# Transmitter_Bug-BC547.net
KiCad netlist of a schematic drawn in EAGLE
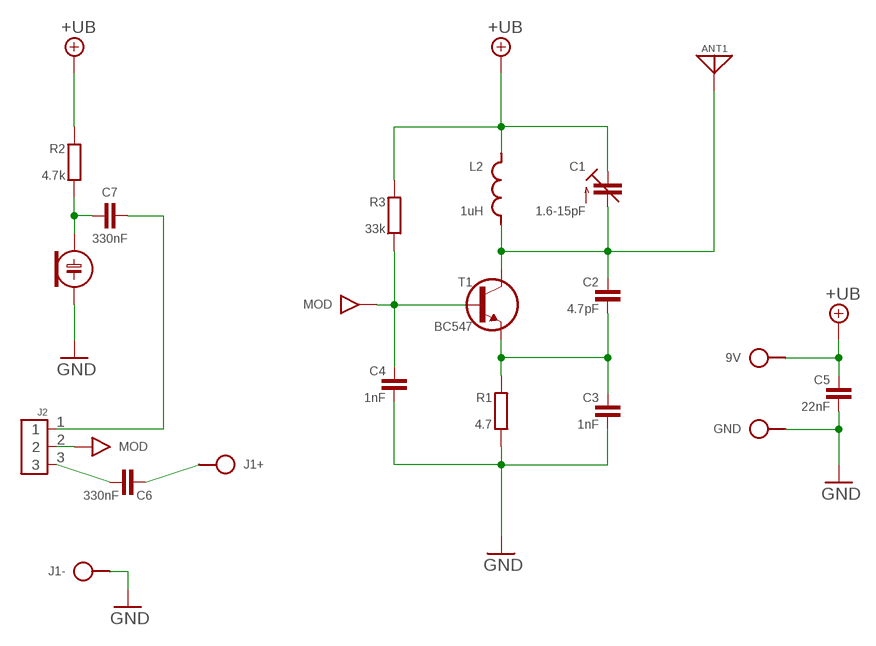
[diagram p0: schematic, sheet 1]

(export (version "E")
  (design (tool "Eeschema 10.0.6"))
  (components
    (comp (ref "9V")
      (value "SPAD")
      (footprint "eagle-import:SPAD")
      (libsource (lib "eagle-import") (part "SPAD"))
    )
    (comp (ref "ANT1")
      (value "ANT")
      (footprint "eagle-import:SPAD")
      (libsource (lib "eagle-import") (part "ANT"))
    )
    (comp (ref "C1")
      (value "1.6-15pF")
      (footprint "eagle-import:TRIM-2222-808")
      (libsource (lib "eagle-import") (part "C-TR-PH201272222-808-2PINB"))
    )
    (comp (ref "C2")
      (value "4.7pF")
      (footprint "eagle-import:C025-015X024")
      (libsource (lib "eagle-import") (part "C025-015X024"))
    )
    (comp (ref "C3")
      (value "1nF")
      (footprint "eagle-import:C025-015X024")
      (libsource (lib "eagle-import") (part "C025-015X024"))
    )
    (comp (ref "C4")
      (value "1nF")
      (footprint "eagle-import:C050-020X036_V")
      (libsource (lib "eagle-import") (part "C050-020X036/V"))
    )
    (comp (ref "C5")
      (value "22nF")
      (footprint "eagle-import:C050-020X036_V")
      (libsource (lib "eagle-import") (part "C050-020X036/V"))
    )
    (comp (ref "C6")
      (value "330nF")
      (footprint "eagle-import:C050-020X044")
      (libsource (lib "eagle-import") (part "C-H050-020X044"))
    )
    (comp (ref "C7")
      (value "330nF")
      (footprint "eagle-import:C050-020X044")
      (libsource (lib "eagle-import") (part "C050-020X044"))
    )
    (comp (ref "ECM")
      (value "ECM-4")
      (footprint "eagle-import:ECM-4")
      (libsource (lib "eagle-import") (part "ECM-4"))
    )
    (comp (ref "GND")
      (value "SPAD")
      (footprint "eagle-import:SPAD")
      (libsource (lib "eagle-import") (part "SPAD"))
    )
    (comp (ref "J1")
      (value "SPAD+--+")
      (footprint "eagle-import:SPAD-+")
      (libsource (lib "eagle-import") (part "SPAD+--+"))
    )
    (comp (ref "J2")
      (value "CONN-3P-3P")
      (footprint "eagle-import:CONN-3P")
      (libsource (lib "eagle-import") (part "CONN-3P-3P"))
    )
    (comp (ref "L2")
      (value "1uH")
      (footprint "eagle-import:L-04_7V-X")
      (libsource (lib "eagle-import") (part "L-SHORT04/7V-X"))
    )
    (comp (ref "R1")
      (value "4.7")
      (footprint "eagle-import:0204_2V")
      (libsource (lib "eagle-import") (part "R0204/2V"))
    )
    (comp (ref "R2")
      (value "4.7k")
      (footprint "eagle-import:0202_7-V")
      (libsource (lib "eagle-import") (part "R0202/7-V"))
    )
    (comp (ref "R3")
      (value "33k")
      (footprint "eagle-import:0202_7-V")
      (libsource (lib "eagle-import") (part "R0202/7-V"))
    )
    (comp (ref "T1")
      (value "BC547")
      (footprint "eagle-import:TO92-CBE")
      (libsource (lib "eagle-import") (part "BC547CBE"))
    )
  )
  (nets
    (net (code "1") (name "+UB") (class "Default")
      (node (ref "9V") (pin "1") (pinfunction "P$1_1") (pintype "passive"))
      (node (ref "C1") (pin "3") (pinfunction "E_3") (pintype "passive"))
      (node (ref "C5") (pin "1") (pinfunction "1_1") (pintype "passive"))
      (node (ref "L2") (pin "2") (pinfunction "2_2") (pintype "passive"))
      (node (ref "R2") (pin "1") (pinfunction "1_1") (pintype "passive"))
      (node (ref "R3") (pin "1") (pinfunction "1_1") (pintype "passive"))
    )
    (net (code "2") (name "GND") (class "Default")
      (node (ref "C3") (pin "2") (pinfunction "2_2") (pintype "passive"))
      (node (ref "C4") (pin "2") (pinfunction "2_2") (pintype "passive"))
      (node (ref "C5") (pin "2") (pinfunction "2_2") (pintype "passive"))
      (node (ref "ECM") (pin "2") (pinfunction "-_2") (pintype "passive"))
      (node (ref "GND") (pin "1") (pinfunction "P$1_1") (pintype "passive"))
      (node (ref "J1") (pin "1") (pinfunction "P$1_1") (pintype "passive"))
      (node (ref "R1") (pin "2") (pinfunction "2_2") (pintype "passive"))
    )
    (net (code "3") (name "MOD") (class "Default")
      (node (ref "C4") (pin "1") (pinfunction "1_1") (pintype "passive"))
      (node (ref "J2") (pin "2") (pinfunction "2_2") (pintype "bidirectional"))
      (node (ref "R3") (pin "2") (pinfunction "2_2") (pintype "passive"))
      (node (ref "T1") (pin "B") (pinfunction "B_B") (pintype "passive"))
    )
    (net (code "4") (name "Net-(C1-A)") (class "Default")
      (node (ref "ANT1") (pin "1") (pinfunction "1_1") (pintype "output"))
      (node (ref "C1") (pin "2") (pinfunction "A_2") (pintype "passive"))
      (node (ref "C2") (pin "1") (pinfunction "1_1") (pintype "passive"))
      (node (ref "L2") (pin "1") (pinfunction "1_1") (pintype "passive"))
      (node (ref "T1") (pin "C") (pinfunction "C_C") (pintype "passive"))
    )
    (net (code "5") (name "Net-(C2-Pad2)") (class "Default")
      (node (ref "C2") (pin "2") (pinfunction "2_2") (pintype "passive"))
      (node (ref "C3") (pin "1") (pinfunction "1_1") (pintype "passive"))
      (node (ref "R1") (pin "1") (pinfunction "1_1") (pintype "passive"))
      (node (ref "T1") (pin "E") (pinfunction "E_E") (pintype "passive"))
    )
    (net (code "6") (name "Net-(C6-Pad2)") (class "Default")
      (node (ref "C6") (pin "2") (pinfunction "2_2") (pintype "passive"))
      (node (ref "J2") (pin "3") (pinfunction "3_3") (pintype "bidirectional"))
    )
    (net (code "7") (name "Net-(C7-Pad2)") (class "Default")
      (node (ref "C7") (pin "2") (pinfunction "2_2") (pintype "passive"))
      (node (ref "J2") (pin "1") (pinfunction "1_1") (pintype "bidirectional"))
    )
    (net (code "8") (name "Net-(ECM-+)") (class "Default")
      (node (ref "C7") (pin "1") (pinfunction "1_1") (pintype "passive"))
      (node (ref "ECM") (pin "1") (pinfunction "+_1") (pintype "passive"))
      (node (ref "R2") (pin "2") (pinfunction "2_2") (pintype "passive"))
    )
    (net (code "9") (name "Net-(J1A-P$1)") (class "Default")
      (node (ref "C6") (pin "1") (pinfunction "1_1") (pintype "passive"))
      (node (ref "J1") (pin "2") (pinfunction "P$1_2") (pintype "passive"))
    )
  )
)
